# MCP4922.net
KiCad netlist of a schematic drawn in EAGLE
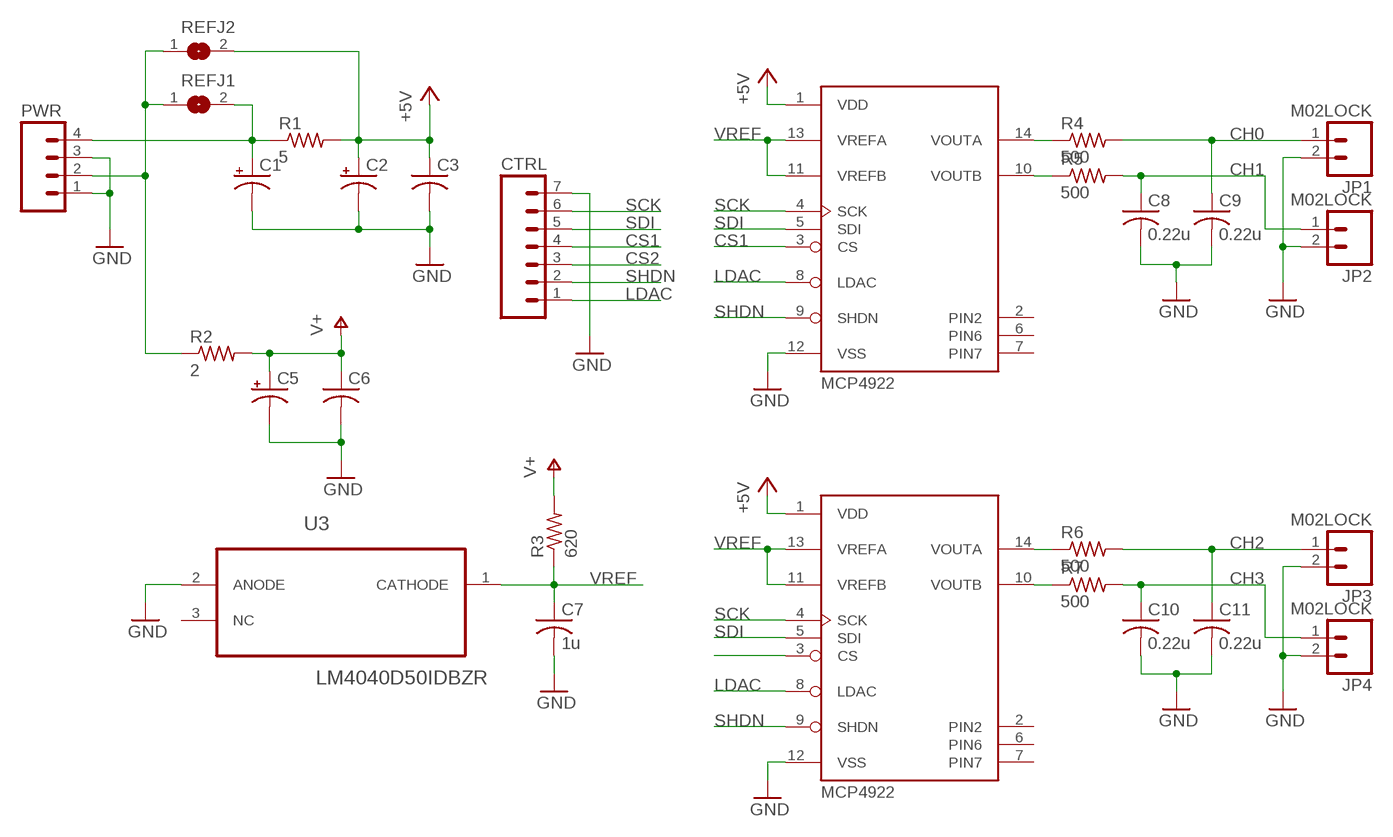
[diagram p0: schematic, sheet 1]

(export (version "E")
  (design (tool "Eeschema 10.0.6"))
  (components
    (comp (ref "C1")
      (value "CPOL-US153CLV-0405")
      (footprint "eagle-import:153CLV-0405")
      (libsource (lib "eagle-import") (part "CPOL-US153CLV-0405"))
    )
    (comp (ref "C2")
      (value "CPOL-US153CLV-0505")
      (footprint "eagle-import:153CLV-0505")
      (libsource (lib "eagle-import") (part "CPOL-US153CLV-0505"))
    )
    (comp (ref "C3")
      (value "C-USC0805")
      (footprint "eagle-import:C0805")
      (libsource (lib "eagle-import") (part "C-USC0805"))
    )
    (comp (ref "C5")
      (value "CPOL-US153CLV-0405")
      (footprint "eagle-import:153CLV-0405")
      (libsource (lib "eagle-import") (part "CPOL-US153CLV-0405"))
    )
    (comp (ref "C6")
      (value "C-USC0805")
      (footprint "eagle-import:C0805")
      (libsource (lib "eagle-import") (part "C-USC0805"))
    )
    (comp (ref "C7")
      (value "1u")
      (footprint "eagle-import:C0805")
      (libsource (lib "eagle-import") (part "C-USC0805"))
    )
    (comp (ref "C8")
      (value "0.22u")
      (footprint "eagle-import:C0805")
      (libsource (lib "eagle-import") (part "C-USC0805"))
    )
    (comp (ref "C9")
      (value "0.22u")
      (footprint "eagle-import:C0805")
      (libsource (lib "eagle-import") (part "C-USC0805"))
    )
    (comp (ref "C10")
      (value "0.22u")
      (footprint "eagle-import:C0805")
      (libsource (lib "eagle-import") (part "C-USC0805"))
    )
    (comp (ref "C11")
      (value "0.22u")
      (footprint "eagle-import:C0805")
      (libsource (lib "eagle-import") (part "C-USC0805"))
    )
    (comp (ref "CTRL")
      (value "M07LOCK")
      (footprint "eagle-import:1X07_LOCK")
      (libsource (lib "eagle-import") (part "M07LOCK"))
    )
    (comp (ref "JP1")
      (value "M02LOCK")
      (footprint "eagle-import:1X02_LOCK")
      (libsource (lib "eagle-import") (part "M02LOCK"))
    )
    (comp (ref "JP2")
      (value "M02LOCK")
      (footprint "eagle-import:1X02_LOCK")
      (libsource (lib "eagle-import") (part "M02LOCK"))
    )
    (comp (ref "JP3")
      (value "M02LOCK")
      (footprint "eagle-import:1X02_LOCK")
      (libsource (lib "eagle-import") (part "M02LOCK"))
    )
    (comp (ref "JP4")
      (value "M02LOCK")
      (footprint "eagle-import:1X02_LOCK")
      (libsource (lib "eagle-import") (part "M02LOCK"))
    )
    (comp (ref "PWR")
      (value "M04LOCK")
      (footprint "eagle-import:1X04_LOCK")
      (libsource (lib "eagle-import") (part "M04LOCK"))
    )
    (comp (ref "R1")
      (value "5")
      (footprint "eagle-import:R0805")
      (libsource (lib "eagle-import") (part "R-US_R0805"))
    )
    (comp (ref "R2")
      (value "2")
      (footprint "eagle-import:R0805")
      (libsource (lib "eagle-import") (part "R-US_R0805"))
    )
    (comp (ref "R3")
      (value "620")
      (footprint "eagle-import:R0805")
      (libsource (lib "eagle-import") (part "R-US_R0805"))
    )
    (comp (ref "R4")
      (value "500")
      (footprint "eagle-import:R0805")
      (libsource (lib "eagle-import") (part "R-US_R0805"))
    )
    (comp (ref "R5")
      (value "500")
      (footprint "eagle-import:R0805")
      (libsource (lib "eagle-import") (part "R-US_R0805"))
    )
    (comp (ref "R6")
      (value "500")
      (footprint "eagle-import:R0805")
      (libsource (lib "eagle-import") (part "R-US_R0805"))
    )
    (comp (ref "R7")
      (value "500")
      (footprint "eagle-import:R0805")
      (libsource (lib "eagle-import") (part "R-US_R0805"))
    )
    (comp (ref "REFJ1")
      (value "SJ")
      (footprint "eagle-import:SJ")
      (libsource (lib "eagle-import") (part "SJ"))
    )
    (comp (ref "REFJ2")
      (value "SJ")
      (footprint "eagle-import:SJ")
      (libsource (lib "eagle-import") (part "SJ"))
    )
    (comp (ref "U1")
      (value "MCP4922")
      (footprint "eagle-import:SO-14")
      (libsource (lib "eagle-import") (part "MCP4922"))
    )
    (comp (ref "U2")
      (value "MCP4922")
      (footprint "eagle-import:SO-14")
      (libsource (lib "eagle-import") (part "MCP4922"))
    )
    (comp (ref "U3")
      (value "LM4040D50IDBZR")
      (footprint "eagle-import:SOT95P237X112-3N")
      (libsource (lib "eagle-import") (part "LM4040D50IDBZR"))
    )
  )
  (nets
    (net (code "1") (name "+5V") (class "Default")
      (node (ref "C2") (pin "+") (pinfunction "+_+") (pintype "passive"))
      (node (ref "C3") (pin "1") (pinfunction "1_1") (pintype "passive"))
      (node (ref "R1") (pin "2") (pinfunction "2_2") (pintype "passive"))
      (node (ref "REFJ2") (pin "2") (pinfunction "2_2") (pintype "passive"))
      (node (ref "U1") (pin "1") (pinfunction "VDD_1") (pintype "power_in"))
      (node (ref "U2") (pin "1") (pinfunction "VDD_1") (pintype "power_in"))
    )
    (net (code "2") (name "/CH0") (class "Default")
      (node (ref "C9") (pin "1") (pinfunction "1_1") (pintype "passive"))
      (node (ref "JP1") (pin "1") (pinfunction "1_1") (pintype "passive"))
      (node (ref "R4") (pin "2") (pinfunction "2_2") (pintype "passive"))
    )
    (net (code "3") (name "/CH1") (class "Default")
      (node (ref "C8") (pin "1") (pinfunction "1_1") (pintype "passive"))
      (node (ref "JP2") (pin "1") (pinfunction "1_1") (pintype "passive"))
      (node (ref "R5") (pin "2") (pinfunction "2_2") (pintype "passive"))
    )
    (net (code "4") (name "/CH2") (class "Default")
      (node (ref "C11") (pin "1") (pinfunction "1_1") (pintype "passive"))
      (node (ref "JP3") (pin "1") (pinfunction "1_1") (pintype "passive"))
      (node (ref "R6") (pin "2") (pinfunction "2_2") (pintype "passive"))
    )
    (net (code "5") (name "/CH3") (class "Default")
      (node (ref "C10") (pin "1") (pinfunction "1_1") (pintype "passive"))
      (node (ref "JP4") (pin "1") (pinfunction "1_1") (pintype "passive"))
      (node (ref "R7") (pin "2") (pinfunction "2_2") (pintype "passive"))
    )
    (net (code "6") (name "/CS1") (class "Default")
      (node (ref "CTRL") (pin "4") (pinfunction "4_4") (pintype "passive"))
      (node (ref "U1") (pin "3") (pinfunction "CS_3") (pintype "input"))
    )
    (net (code "7") (name "/CS2") (class "Default")
      (node (ref "CTRL") (pin "3") (pinfunction "3_3") (pintype "passive"))
      (node (ref "U2") (pin "3") (pinfunction "CS_3") (pintype "input"))
    )
    (net (code "8") (name "/LDAC") (class "Default")
      (node (ref "CTRL") (pin "1") (pinfunction "1_1") (pintype "passive"))
      (node (ref "U1") (pin "8") (pinfunction "LDAC_8") (pintype "input"))
      (node (ref "U2") (pin "8") (pinfunction "LDAC_8") (pintype "input"))
    )
    (net (code "9") (name "/SCK") (class "Default")
      (node (ref "CTRL") (pin "6") (pinfunction "6_6") (pintype "passive"))
      (node (ref "U1") (pin "4") (pinfunction "SCK_4") (pintype "input"))
      (node (ref "U2") (pin "4") (pinfunction "SCK_4") (pintype "input"))
    )
    (net (code "10") (name "/SDI") (class "Default")
      (node (ref "CTRL") (pin "5") (pinfunction "5_5") (pintype "passive"))
      (node (ref "U1") (pin "5") (pinfunction "SDI_5") (pintype "input"))
      (node (ref "U2") (pin "5") (pinfunction "SDI_5") (pintype "input"))
    )
    (net (code "11") (name "/SHDN") (class "Default")
      (node (ref "CTRL") (pin "2") (pinfunction "2_2") (pintype "passive"))
      (node (ref "U1") (pin "9") (pinfunction "SHDN_9") (pintype "input"))
      (node (ref "U2") (pin "9") (pinfunction "SHDN_9") (pintype "input"))
    )
    (net (code "12") (name "/VREF") (class "Default")
      (node (ref "C7") (pin "1") (pinfunction "1_1") (pintype "passive"))
      (node (ref "R3") (pin "1") (pinfunction "1_1") (pintype "passive"))
      (node (ref "U1") (pin "11") (pinfunction "VREFB_11") (pintype "input"))
      (node (ref "U1") (pin "13") (pinfunction "VREFA_13") (pintype "input"))
      (node (ref "U2") (pin "11") (pinfunction "VREFB_11") (pintype "input"))
      (node (ref "U2") (pin "13") (pinfunction "VREFA_13") (pintype "input"))
      (node (ref "U3") (pin "1") (pinfunction "CATHODE_1") (pintype "output"))
    )
    (net (code "13") (name "GND") (class "Default")
      (node (ref "C1") (pin "-") (pinfunction "-_-") (pintype "passive"))
      (node (ref "C10") (pin "2") (pinfunction "2_2") (pintype "passive"))
      (node (ref "C11") (pin "2") (pinfunction "2_2") (pintype "passive"))
      (node (ref "C2") (pin "-") (pinfunction "-_-") (pintype "passive"))
      (node (ref "C3") (pin "2") (pinfunction "2_2") (pintype "passive"))
      (node (ref "C5") (pin "-") (pinfunction "-_-") (pintype "passive"))
      (node (ref "C6") (pin "2") (pinfunction "2_2") (pintype "passive"))
      (node (ref "C7") (pin "2") (pinfunction "2_2") (pintype "passive"))
      (node (ref "C8") (pin "2") (pinfunction "2_2") (pintype "passive"))
      (node (ref "C9") (pin "2") (pinfunction "2_2") (pintype "passive"))
      (node (ref "CTRL") (pin "7") (pinfunction "7_7") (pintype "passive"))
      (node (ref "JP1") (pin "2") (pinfunction "2_2") (pintype "passive"))
      (node (ref "JP2") (pin "2") (pinfunction "2_2") (pintype "passive"))
      (node (ref "JP3") (pin "2") (pinfunction "2_2") (pintype "passive"))
      (node (ref "JP4") (pin "2") (pinfunction "2_2") (pintype "passive"))
      (node (ref "PWR") (pin "1") (pinfunction "1_1") (pintype "passive"))
      (node (ref "PWR") (pin "3") (pinfunction "3_3") (pintype "passive"))
      (node (ref "U1") (pin "12") (pinfunction "VSS_12") (pintype "power_in"))
      (node (ref "U2") (pin "12") (pinfunction "VSS_12") (pintype "power_in"))
      (node (ref "U3") (pin "2") (pinfunction "ANODE_2") (pintype "input"))
    )
    (net (code "14") (name "Net-(C1-Pad+)") (class "Default")
      (node (ref "C1") (pin "+") (pinfunction "+_+") (pintype "passive"))
      (node (ref "PWR") (pin "4") (pinfunction "4_4") (pintype "passive"))
      (node (ref "R1") (pin "1") (pinfunction "1_1") (pintype "passive"))
      (node (ref "REFJ1") (pin "2") (pinfunction "2_2") (pintype "passive"))
    )
    (net (code "15") (name "Net-(PWR-Pad2)") (class "Default")
      (node (ref "PWR") (pin "2") (pinfunction "2_2") (pintype "passive"))
      (node (ref "R2") (pin "1") (pinfunction "1_1") (pintype "passive"))
      (node (ref "REFJ1") (pin "1") (pinfunction "1_1") (pintype "passive"))
      (node (ref "REFJ2") (pin "1") (pinfunction "1_1") (pintype "passive"))
    )
    (net (code "16") (name "Net-(U1-VOUTA)") (class "Default")
      (node (ref "R4") (pin "1") (pinfunction "1_1") (pintype "passive"))
      (node (ref "U1") (pin "14") (pinfunction "VOUTA_14") (pintype "output"))
    )
    (net (code "17") (name "Net-(U1-VOUTB)") (class "Default")
      (node (ref "R5") (pin "1") (pinfunction "1_1") (pintype "passive"))
      (node (ref "U1") (pin "10") (pinfunction "VOUTB_10") (pintype "output"))
    )
    (net (code "18") (name "Net-(U2-VOUTA)") (class "Default")
      (node (ref "R6") (pin "1") (pinfunction "1_1") (pintype "passive"))
      (node (ref "U2") (pin "14") (pinfunction "VOUTA_14") (pintype "output"))
    )
    (net (code "19") (name "Net-(U2-VOUTB)") (class "Default")
      (node (ref "R7") (pin "1") (pinfunction "1_1") (pintype "passive"))
      (node (ref "U2") (pin "10") (pinfunction "VOUTB_10") (pintype "output"))
    )
    (net (code "20") (name "V+") (class "Default")
      (node (ref "C5") (pin "+") (pinfunction "+_+") (pintype "passive"))
      (node (ref "C6") (pin "1") (pinfunction "1_1") (pintype "passive"))
      (node (ref "R2") (pin "2") (pinfunction "2_2") (pintype "passive"))
      (node (ref "R3") (pin "2") (pinfunction "2_2") (pintype "passive"))
    )
    (net (code "21") (name "unconnected-(U1-PIN2-Pad2)") (class "Default")
      (node (ref "U1") (pin "2") (pinfunction "PIN2_2") (pintype "no_connect"))
    )
    (net (code "22") (name "unconnected-(U1-PIN6-Pad6)") (class "Default")
      (node (ref "U1") (pin "6") (pinfunction "PIN6_6") (pintype "no_connect"))
    )
    (net (code "23") (name "unconnected-(U1-PIN7-Pad7)") (class "Default")
      (node (ref "U1") (pin "7") (pinfunction "PIN7_7") (pintype "no_connect"))
    )
    (net (code "24") (name "unconnected-(U2-PIN2-Pad2)") (class "Default")
      (node (ref "U2") (pin "2") (pinfunction "PIN2_2") (pintype "no_connect"))
    )
    (net (code "25") (name "unconnected-(U2-PIN6-Pad6)") (class "Default")
      (node (ref "U2") (pin "6") (pinfunction "PIN6_6") (pintype "no_connect"))
    )
    (net (code "26") (name "unconnected-(U2-PIN7-Pad7)") (class "Default")
      (node (ref "U2") (pin "7") (pinfunction "PIN7_7") (pintype "no_connect"))
    )
    (net (code "27") (name "unconnected-(U3-NC-Pad3)") (class "Default")
      (node (ref "U3") (pin "3") (pinfunction "NC_3") (pintype "no_connect"))
    )
  )
)
